# GPS.net
KiCad netlist of a schematic drawn in Altium Designer
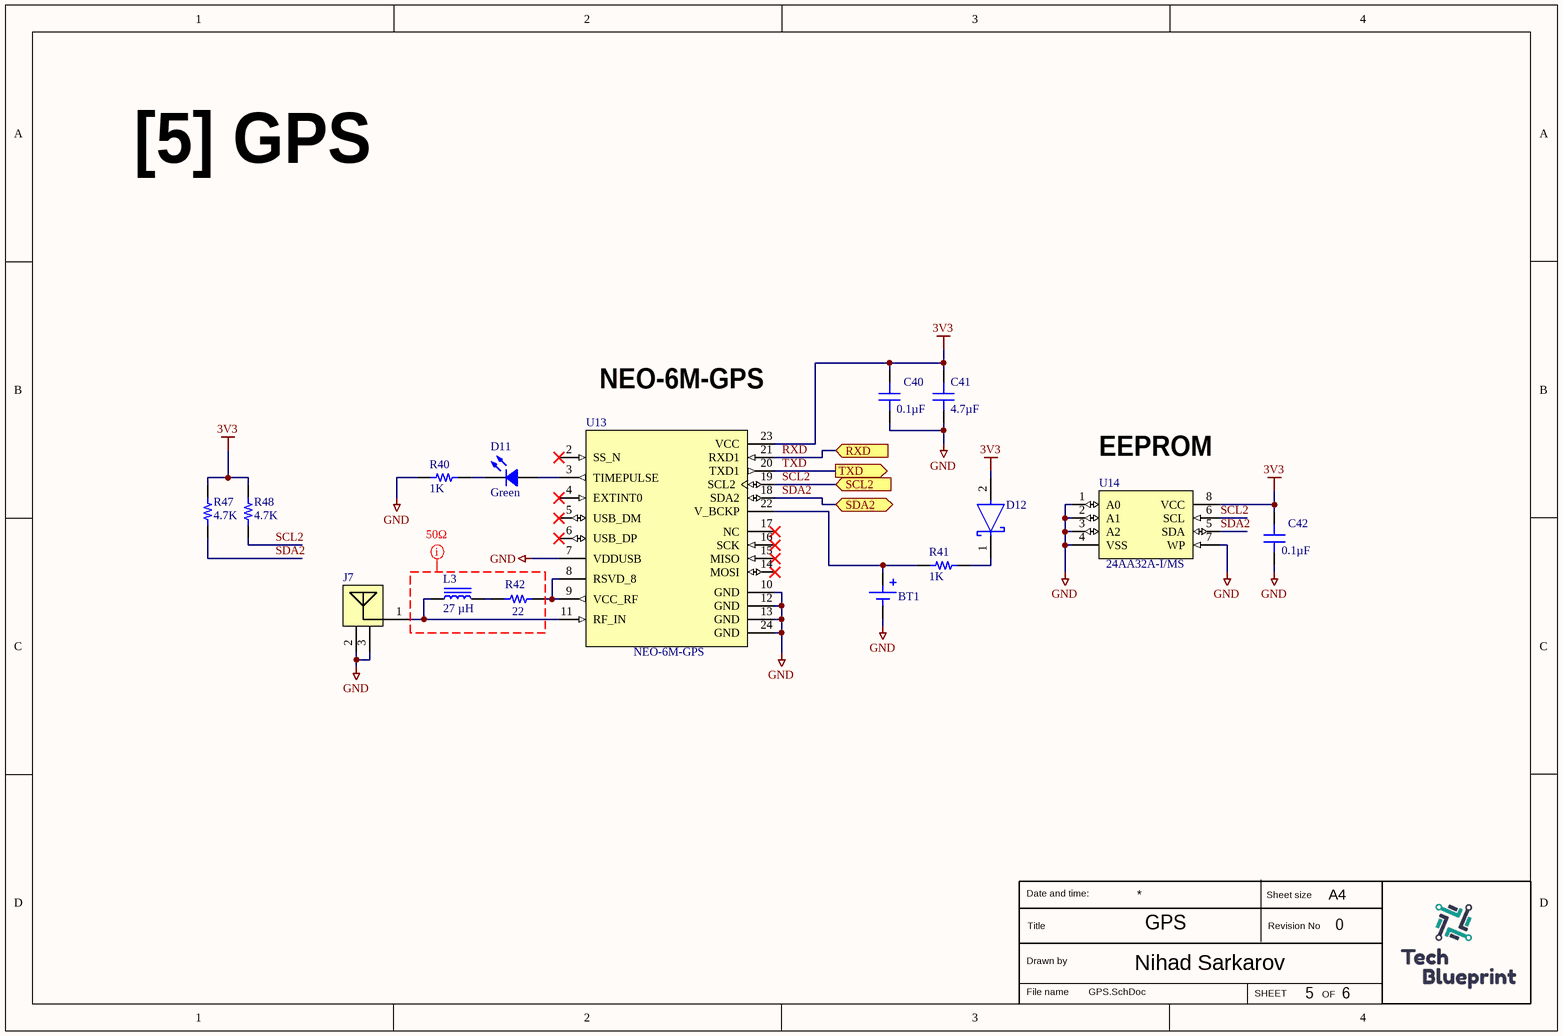
[diagram p0: GPS.SchDoc]

(export (version "E")
  (design (tool "Eeschema 10.0.6"))
  (components
    (comp (ref "BT1")
      (value "MS621FE-FL11E")
      (footprint "MS621FE-FL11E:BAT_MS621FE-FL11E")
      (fields (field (name "MF") "{'manufacturer': u'Seiko Instruments'}"))
      (libsource (lib "Schlib1") (part "MS621FE-FL11E"))
    )
    (comp (ref "C40")
      (value "0.1µF")
      (footprint "CAP 0805_2012")
      (description "CAP CER 0.1UF 25V X7R 0805")
      (fields
        (field (name "PART NUMBER") "08053C104KAT4A")
        (field (name "CAPACITANCE") "0.1µF")
        (field (name "MANUFACTURER") "AVX Corporation")
      )
      (libsource (lib "Celestial Altium Library - altium_library") (part "Capacitor"))
    )
    (comp (ref "C41")
      (value "4.7µF")
      (footprint "CAP 0805_2012")
      (description "CAP CER 4.7UF 10V X5R 0805")
      (fields
        (field (name "PART NUMBER") "0805ZD475KAT2A")
        (field (name "CAPACITANCE") "4.7µF")
        (field (name "MANUFACTURER") "AVX Corporation")
      )
      (libsource (lib "Celestial Altium Library - altium_library") (part "Capacitor"))
    )
    (comp (ref "C42")
      (value "0.1µF")
      (footprint "CAP 0805_2012")
      (description "CAP CER 0.1UF 25V X7R 0805")
      (fields
        (field (name "PART NUMBER") "08053C104KAT4A")
        (field (name "CAPACITANCE") "0.1µF")
        (field (name "MANUFACTURER") "AVX Corporation")
      )
      (libsource (lib "Celestial Altium Library - altium_library") (part "Capacitor"))
    )
    (comp (ref "D11")
      (value "Green")
      (footprint "LED 0603_1608 GREEN")
      (description "LED GREEN CLEAR CHIP 0603 SMD")
      (fields
        (field (name "PART NUMBER") "LSM0603453V")
        (field (name "MANUFACTURER") "Visual Communications Company - VCC")
      )
      (libsource (lib "Celestial Altium Library - altium_library") (part "LED"))
    )
    (comp (ref "D12")
      (value "B0530WS-7-F")
      (footprint "FP-SOD323-MFG")
      (description "DIODE SCHOTTKY 30V 500MA SOD323")
      (fields
        (field (name "MANUFACTURER") "Diodes Inc.")
        (field (name "OCTOPART") "https://octopart.com/b0530ws-7-f-diodes+inc.-325723")
      )
      (libsource (lib "Altium Content Vault") (part "1d6ec82d83fb6aee721767c19dac4b9"))
    )
    (comp (ref "J7")
      (value "U.FL-R-SMT-1(10)")
      (footprint "FP-U_FL-R-SMT-1_10-MFG")
      (description "CONN U.FL RCPT STR 50 OHM SMD")
      (libsource (lib "Schlib1") (part "CMP-2000-05152-3"))
    )
    (comp (ref "L3")
      (value "27 µH")
      (footprint "TDK MLF1608")
      (description "FIXED IND 27UH 2MA 1.8 OHM SMD")
      (fields (field (name "PART NUMBER") "MLF1608C270KTD00") (field (name "MANUFACTURER") "TDK Corporation"))
      (libsource (lib "Celestial Altium Library - altium_library") (part "Inductor"))
    )
    (comp (ref "R40")
      (value "1K")
      (footprint "RES 0603_1608")
      (description "RES 1K OHM 5% 1/10W 0603")
      (fields
        (field (name "PART NUMBER") "RMCF0603JT1K00")
        (field (name "MANUFACTURER") "Stackpole Electronics Inc")
      )
      (libsource (lib "Celestial Altium Library - altium_library") (part "Resistor"))
    )
    (comp (ref "R41")
      (value "1K")
      (footprint "RES 0805_2012")
      (description "RES SMD 1K OHM 5% 1/3W 0805")
      (fields
        (field (name "PART NUMBER") "CRGH0805J1K0")
        (field (name "MANUFACTURER") "TE Connectivity Passive Product")
      )
      (libsource (lib "Celestial Altium Library - altium_library") (part "Resistor"))
    )
    (comp (ref "R42")
      (value "22")
      (footprint "RES 0603_1608")
      (description "RES SMD 22 OHM 1% 1/10W 0603")
      (fields
        (field (name "PART NUMBER") "ERJ-3EKF22R0V")
        (field (name "MANUFACTURER") "Panasonic Electronic Components")
      )
      (libsource (lib "Celestial Altium Library - altium_library") (part "Resistor"))
    )
    (comp (ref "R47")
      (value "4.7K")
      (footprint "KOA RES RK73 RN73 0603_1608")
      (description "RES 4.7K OHM 5% 1/10W 0603")
      (fields
        (field (name "PART NUMBER") "RK73B1JTTD472J")
        (field (name "MANUFACTURER") "KOA Speer Electronics, Inc.")
      )
      (libsource (lib "Celestial Altium Library - altium_library") (part "Resistor"))
    )
    (comp (ref "R48")
      (value "4.7K")
      (footprint "KOA RES RK73 RN73 0603_1608")
      (description "RES 4.7K OHM 5% 1/10W 0603")
      (fields
        (field (name "PART NUMBER") "RK73B1JTTD472J")
        (field (name "MANUFACTURER") "KOA Speer Electronics, Inc.")
      )
      (libsource (lib "Celestial Altium Library - altium_library") (part "Resistor"))
    )
    (comp (ref "U13")
      (value "NEO-6M-GPS")
      (footprint "NEO-6M-GPS:XCVR_NEO-6M-GPS")
      (fields (field (name "MF") "{'manufacturer': u'u-blox'}"))
      (libsource (lib "Schlib1") (part "NEO-6M-GPS"))
    )
    (comp (ref "U14")
      (value "24AA32A-I/MS")
      (footprint "24AA32A-I_MS:SOP65P490X110-8N")
      (fields (field (name "MF") "{'manufacturer': u'Microchip Technology'}"))
      (libsource (lib "Schlib1") (part "24AA32A-I/MS"))
    )
  )
  (nets
    (net (code "1") (name "/RXD") (class "Default")
      (node (ref "U13") (pin "21") (pinfunction "RXD1_21") (pintype "input"))
    )
    (net (code "2") (name "/SCL2") (class "Default")
      (node (ref "R48") (pin "1") (pinfunction "1_1") (pintype "passive"))
      (node (ref "U13") (pin "19") (pinfunction "SCL2_19") (pintype "bidirectional"))
      (node (ref "U14") (pin "6") (pinfunction "SCL_6") (pintype "input"))
    )
    (net (code "3") (name "/SDA2") (class "Default")
      (node (ref "R47") (pin "1") (pinfunction "1_1") (pintype "passive"))
      (node (ref "U13") (pin "18") (pinfunction "SDA2_18") (pintype "bidirectional"))
      (node (ref "U14") (pin "5") (pinfunction "SDA_5") (pintype "bidirectional"))
    )
    (net (code "4") (name "/TXD") (class "Default")
      (node (ref "U13") (pin "20") (pinfunction "TXD1_20") (pintype "output"))
    )
    (net (code "5") (name "3V3") (class "Default")
      (node (ref "C40") (pin "2") (pinfunction "2_2") (pintype "passive"))
      (node (ref "C41") (pin "2") (pinfunction "2_2") (pintype "passive"))
      (node (ref "C42") (pin "2") (pinfunction "2_2") (pintype "passive"))
      (node (ref "D12") (pin "2") (pinfunction "A_2") (pintype "passive"))
      (node (ref "R47") (pin "2") (pinfunction "2_2") (pintype "passive"))
      (node (ref "R48") (pin "2") (pinfunction "2_2") (pintype "passive"))
      (node (ref "U13") (pin "23") (pinfunction "VCC_23") (pintype "power_in"))
      (node (ref "U14") (pin "8") (pinfunction "VCC_8") (pintype "power_in"))
    )
    (net (code "6") (name "GND") (class "Default")
      (node (ref "BT1") (pin "NEG") (pinfunction "NEG_NEG") (pintype "passive"))
      (node (ref "C40") (pin "1") (pinfunction "1_1") (pintype "passive"))
      (node (ref "C41") (pin "1") (pinfunction "1_1") (pintype "passive"))
      (node (ref "C42") (pin "1") (pinfunction "1_1") (pintype "passive"))
      (node (ref "J7") (pin "2") (pinfunction "GND_2") (pintype "passive"))
      (node (ref "J7") (pin "3") (pinfunction "GND_3") (pintype "passive"))
      (node (ref "R40") (pin "1") (pinfunction "1_1") (pintype "passive"))
      (node (ref "U13") (pin "10") (pinfunction "GND_10") (pintype "passive"))
      (node (ref "U13") (pin "12") (pinfunction "GND_12") (pintype "passive"))
      (node (ref "U13") (pin "13") (pinfunction "GND_13") (pintype "passive"))
      (node (ref "U13") (pin "24") (pinfunction "GND_24") (pintype "passive"))
      (node (ref "U13") (pin "7") (pinfunction "VDDUSB_7") (pintype "power_in"))
      (node (ref "U14") (pin "1") (pinfunction "A0_1") (pintype "bidirectional"))
      (node (ref "U14") (pin "2") (pinfunction "A1_2") (pintype "bidirectional"))
      (node (ref "U14") (pin "3") (pinfunction "A2_3") (pintype "bidirectional"))
      (node (ref "U14") (pin "4") (pinfunction "VSS_4") (pintype "power_in"))
      (node (ref "U14") (pin "7") (pinfunction "WP_7") (pintype "input"))
    )
    (net (code "7") (name "Net-(D11-Pad2)") (class "Default")
      (node (ref "D11") (pin "2") (pinfunction "2_2") (pintype "passive"))
      (node (ref "R40") (pin "2") (pinfunction "2_2") (pintype "passive"))
    )
    (net (code "8") (name "Net-(D12-C)") (class "Default")
      (node (ref "D12") (pin "1") (pinfunction "C_1") (pintype "passive"))
      (node (ref "R41") (pin "2") (pinfunction "2_2") (pintype "passive"))
    )
    (net (code "9") (name "Net-(J7-SIG)") (class "Default")
      (node (ref "J7") (pin "1") (pinfunction "SIG_1") (pintype "passive"))
      (node (ref "L3") (pin "1") (pinfunction "1_1") (pintype "passive"))
      (node (ref "U13") (pin "11") (pinfunction "RF_IN_11") (pintype "input"))
    )
    (net (code "10") (name "Net-(L3-Pad2)") (class "Default")
      (node (ref "L3") (pin "2") (pinfunction "2_2") (pintype "passive"))
      (node (ref "R42") (pin "1") (pinfunction "1_1") (pintype "passive"))
    )
    (net (code "11") (name "Net-(U13-RSVD_8)") (class "Default")
      (node (ref "R42") (pin "2") (pinfunction "2_2") (pintype "passive"))
      (node (ref "U13") (pin "8") (pinfunction "RSVD_8_8") (pintype "passive"))
      (node (ref "U13") (pin "9") (pinfunction "VCC_RF_9") (pintype "output"))
    )
    (net (code "12") (name "Net-(U13-TIMEPULSE)") (class "Default")
      (node (ref "D11") (pin "1") (pinfunction "1_1") (pintype "passive"))
      (node (ref "U13") (pin "3") (pinfunction "TIMEPULSE_3") (pintype "output"))
    )
    (net (code "13") (name "Net-(U13-V_BCKP)") (class "Default")
      (node (ref "BT1") (pin "POS") (pinfunction "POS_POS") (pintype "passive"))
      (node (ref "R41") (pin "1") (pinfunction "1_1") (pintype "passive"))
      (node (ref "U13") (pin "22") (pinfunction "V_BCKP_22") (pintype "power_in"))
    )
    (net (code "14") (name "unconnected-(U13-EXTINT0-Pad4)") (class "Default")
      (node (ref "U13") (pin "4") (pinfunction "EXTINT0_4") (pintype "input+no_connect"))
    )
    (net (code "15") (name "unconnected-(U13-MISO-Pad15)") (class "Default")
      (node (ref "U13") (pin "15") (pinfunction "MISO_15") (pintype "input+no_connect"))
    )
    (net (code "16") (name "unconnected-(U13-MOSI-Pad14)") (class "Default")
      (node (ref "U13") (pin "14") (pinfunction "MOSI_14") (pintype "bidirectional+no_connect"))
    )
    (net (code "17") (name "unconnected-(U13-NC-Pad17)") (class "Default")
      (node (ref "U13") (pin "17") (pinfunction "NC_17") (pintype "passive+no_connect"))
    )
    (net (code "18") (name "unconnected-(U13-SCK-Pad16)") (class "Default")
      (node (ref "U13") (pin "16") (pinfunction "SCK_16") (pintype "input+no_connect"))
    )
    (net (code "19") (name "unconnected-(U13-SS_N-Pad2)") (class "Default")
      (node (ref "U13") (pin "2") (pinfunction "SS_N_2") (pintype "input+no_connect"))
    )
    (net (code "20") (name "unconnected-(U13-USB_DM-Pad5)") (class "Default")
      (node (ref "U13") (pin "5") (pinfunction "USB_DM_5") (pintype "bidirectional+no_connect"))
    )
    (net (code "21") (name "unconnected-(U13-USB_DP-Pad6)") (class "Default")
      (node (ref "U13") (pin "6") (pinfunction "USB_DP_6") (pintype "bidirectional+no_connect"))
    )
  )
)
